# CH32V307WCU6-R0.net
KiCad netlist of a schematic drawn in Altium Designer
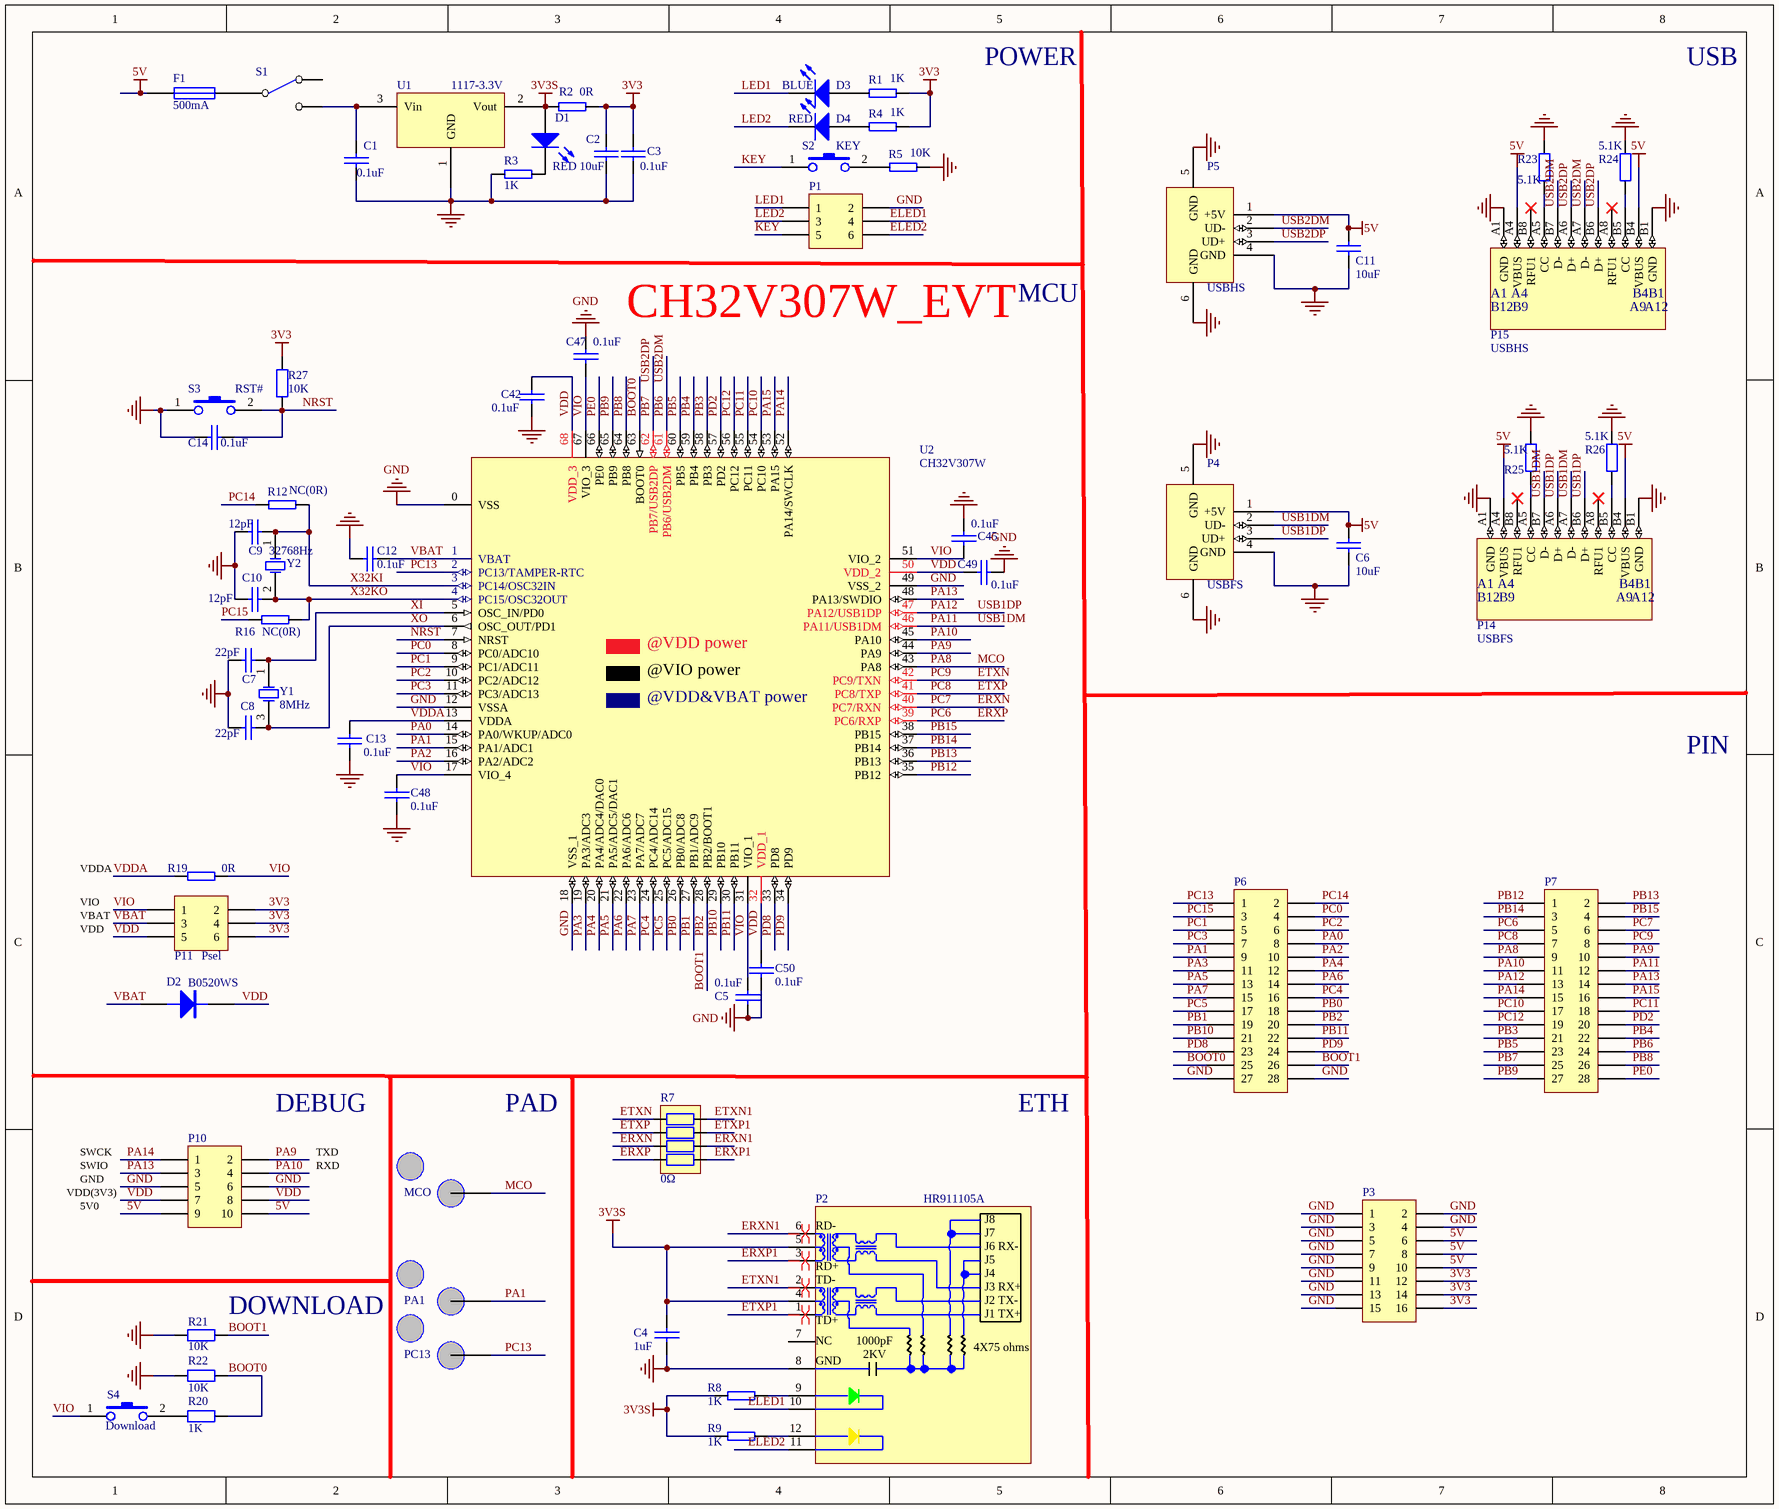
[diagram p0: CH32V307WCU6-R0.SchDoc]

(export (version "E")
  (design (tool "Eeschema 10.0.6"))
  (components
    (comp (ref "C1")
      (value "0.1uF")
      (footprint "0603_C")
      (description "Capacitor")
      (libsource (lib "*") (part "CAP"))
    )
    (comp (ref "C2")
      (value "10uF")
      (footprint "3216_C")
      (description "Capacitor")
      (libsource (lib "*") (part "CAP"))
    )
    (comp (ref "C3")
      (value "0.1uF")
      (footprint "0603_C")
      (description "Capacitor")
      (libsource (lib "*") (part "CAP"))
    )
    (comp (ref "C4")
      (value "1uF")
      (footprint "0603_C")
      (description "Capacitor")
      (libsource (lib "*") (part "CAP"))
    )
    (comp (ref "C5")
      (value "0.1uF")
      (footprint "0603_C")
      (description "Capacitor")
      (libsource (lib "*") (part "CAP"))
    )
    (comp (ref "C6")
      (value "10uF")
      (footprint "3216_C")
      (description "Capacitor")
      (libsource (lib "") (part "CAP_1"))
    )
    (comp (ref "C7")
      (value "22pF")
      (footprint "0603_C")
      (description "Capacitor")
      (libsource (lib "*") (part "CAP"))
    )
    (comp (ref "C8")
      (value "22pF")
      (footprint "0603_C")
      (description "Capacitor")
      (libsource (lib "*") (part "CAP"))
    )
    (comp (ref "C9")
      (value "12pF")
      (footprint "0603_C")
      (description "Capacitor")
      (libsource (lib "*") (part "CAP"))
    )
    (comp (ref "C10")
      (value "12pF")
      (footprint "0603_C")
      (description "Capacitor")
      (libsource (lib "*") (part "CAP"))
    )
    (comp (ref "C11")
      (value "10uF")
      (footprint "3216_C")
      (description "Capacitor")
      (libsource (lib "") (part "CAP_1"))
    )
    (comp (ref "C12")
      (value "0.1uF")
      (footprint "0603_C")
      (description "Capacitor")
      (libsource (lib "*") (part "CAP"))
    )
    (comp (ref "C13")
      (value "0.1uF")
      (footprint "0603_C")
      (description "Capacitor")
      (libsource (lib "*") (part "CAP"))
    )
    (comp (ref "C14")
      (value "0.1uF")
      (footprint "0603_C")
      (description "Capacitor")
      (libsource (lib "") (part "CAP_1"))
    )
    (comp (ref "C42")
      (value "0.1uF")
      (footprint "0603_C")
      (description "Capacitor")
      (libsource (lib "*") (part "CAP"))
    )
    (comp (ref "C45")
      (value "0.1uF")
      (footprint "0603_C")
      (description "Capacitor")
      (libsource (lib "*") (part "CAP"))
    )
    (comp (ref "C47")
      (value "0.1uF")
      (footprint "0603_C")
      (description "Capacitor")
      (libsource (lib "*") (part "CAP"))
    )
    (comp (ref "C48")
      (value "0.1uF")
      (footprint "0603_C")
      (description "Capacitor")
      (libsource (lib "*") (part "CAP"))
    )
    (comp (ref "C49")
      (value "0.1uF")
      (footprint "0603_C")
      (description "Capacitor")
      (libsource (lib "*") (part "CAP"))
    )
    (comp (ref "C50")
      (value "0.1uF")
      (footprint "0603_C")
      (description "Capacitor")
      (libsource (lib "*") (part "CAP"))
    )
    (comp (ref "D1")
      (value "RED")
      (footprint "0603+")
      (description "Typical INFRARED GaAs LED")
      (fields (field (name "PUBLISHER") "Altium Limited"))
      (libsource (lib "*") (part "LED0"))
    )
    (comp (ref "D2")
      (value "B0520WS")
      (footprint "SOD-323")
      (description "Diode")
      (libsource (lib "*") (part "DIODE"))
    )
    (comp (ref "D3")
      (value "BLUE")
      (footprint "0603+")
      (description "Typical INFRARED GaAs LED")
      (fields (field (name "PUBLISHER") "Altium Limited"))
      (libsource (lib "*") (part "LED0"))
    )
    (comp (ref "D4")
      (value "RED")
      (footprint "0603+")
      (description "Typical INFRARED GaAs LED")
      (fields (field (name "PUBLISHER") "Altium Limited"))
      (libsource (lib "*") (part "LED0"))
    )
    (comp (ref "F1")
      (value "500mA")
      (footprint "0603")
      (description "Fuse")
      (libsource (lib "wch_sch_others") (part "FUSE1"))
    )
    (comp (ref "MCO")
      (value "Testpoint")
      (footprint "TESTPOINT1")
      (description "测试点")
      (libsource (lib "wch_sch_others") (part "Testpoint"))
    )
    (comp (ref "P1")
      (value "IO")
      (footprint "IDC6-2.54mm")
      (description "Header, 3-Pin, Dual row, Right Angle")
      (fields (field (name "PUBLISHER") "Altium Limited"))
      (libsource (lib "Miscellaneous Connectors") (part "Header 3X2H"))
    )
    (comp (ref "P2") (value "HR911105A") (footprint "HR911105A") (libsource (lib "*") (part "HR911105A")))
    (comp (ref "P3")
      (value "Ppin")
      (footprint "IDC16-2.54mm")
      (description "Header, 8-Pin, Dual row, Right Angle")
      (fields (field (name "PUBLISHER") "Altium Limited"))
      (libsource (lib "Miscellaneous Connectors") (part "Header 8X2H"))
    )
    (comp (ref "P4")
      (value "USBFS")
      (footprint "USBAF")
      (description "USB Port")
      (libsource (lib "*") (part "USB"))
    )
    (comp (ref "P5")
      (value "USBHS")
      (footprint "USBAF")
      (description "USB Port")
      (libsource (lib "*") (part "USB"))
    )
    (comp (ref "P6")
      (value "HEADER 14x2")
      (footprint "MYPCB:IDC28-2.54MM")
      (description "Header, 14-Pin, Dual row")
      (libsource (lib "wch_sch_others") (part "HEADER 14x2"))
    )
    (comp (ref "P7")
      (value "HEADER 14x2")
      (footprint "MYPCB:IDC28-2.54MM")
      (description "Header, 14-Pin, Dual row")
      (libsource (lib "wch_sch_others") (part "HEADER 14x2"))
    )
    (comp (ref "P10")
      (value "LINK")
      (footprint "IDC10-2.54mm")
      (description "Header, 5-Pin, Dual row, Right Angle")
      (fields (field (name "PUBLISHER") "Altium Limited"))
      (libsource (lib "Miscellaneous Connectors") (part "Header 5X2H"))
    )
    (comp (ref "P11")
      (value "Psel")
      (footprint "IDC6-2.54mm")
      (description "Header, 3-Pin, Dual row, Right Angle")
      (fields (field (name "PUBLISHER") "Altium Limited"))
      (libsource (lib "Miscellaneous Connectors") (part "Header 3X2H"))
    )
    (comp (ref "P14")
      (value "USBFS")
      (footprint "TYPE-C-Receptacle-2.0")
      (libsource (lib "*") (part "TYPE-C1"))
    )
    (comp (ref "P15")
      (value "USBHS")
      (footprint "TYPE-C-Receptacle-2.0")
      (libsource (lib "*") (part "TYPE-C1"))
    )
    (comp (ref "PA1")
      (value "Testpoint")
      (footprint "TESTPOINT1")
      (description "测试点")
      (libsource (lib "wch_sch_others") (part "Testpoint"))
    )
    (comp (ref "PC13")
      (value "Testpoint")
      (footprint "TESTPOINT1")
      (description "测试点")
      (libsource (lib "wch_sch_others") (part "Testpoint"))
    )
    (comp (ref "R1") (value "1K") (footprint "0603") (libsource (lib "wch_sch_others") (part "RES")))
    (comp (ref "R2") (value "0R") (footprint "0603") (libsource (lib "wch_sch_others") (part "RES")))
    (comp (ref "R3") (value "1K") (footprint "0603") (libsource (lib "wch_sch_others") (part "RES")))
    (comp (ref "R4") (value "1K") (footprint "0603") (libsource (lib "wch_sch_others") (part "RES")))
    (comp (ref "R5") (value "10K") (footprint "0603") (libsource (lib "wch_sch_others") (part "RES")))
    (comp (ref "R7")
      (value "0Ω")
      (footprint "8P4R-0603")
      (description "贴片网络排阻")
      (fields (field (name "版权归属") "源创客"))
      (libsource (lib "wch_sch_others") (part "R-8P4R"))
    )
    (comp (ref "R8") (value "1K") (footprint "0603") (libsource (lib "wch_sch_others") (part "RES")))
    (comp (ref "R9") (value "1K") (footprint "0603") (libsource (lib "wch_sch_others") (part "RES")))
    (comp (ref "R12") (value "NC(0R)") (footprint "0603") (libsource (lib "wch_sch_others") (part "RES")))
    (comp (ref "R16") (value "NC(0R)") (footprint "0603") (libsource (lib "wch_sch_others") (part "RES")))
    (comp (ref "R19") (value "0R") (footprint "0603") (libsource (lib "*") (part "R")))
    (comp (ref "R20")
      (value "1K")
      (footprint "0603")
      (description "Resistor")
      (fields (field (name "PUBLISHER") "Altium Limited"))
      (libsource (lib "Miscellaneous Devices") (part "Res2"))
    )
    (comp (ref "R21")
      (value "10K")
      (footprint "0603")
      (description "Resistor")
      (fields (field (name "PUBLISHER") "Altium Limited"))
      (libsource (lib "Miscellaneous Devices") (part "Res2"))
    )
    (comp (ref "R22")
      (value "10K")
      (footprint "0603")
      (description "Resistor")
      (fields (field (name "PUBLISHER") "Altium Limited"))
      (libsource (lib "Miscellaneous Devices") (part "Res2"))
    )
    (comp (ref "R23")
      (value "5.1K")
      (footprint "0603")
      (description "Resistor")
      (libsource (lib "") (part "Res2_1"))
    )
    (comp (ref "R24")
      (value "5.1K")
      (footprint "0603")
      (description "Resistor")
      (libsource (lib "") (part "Res2_1"))
    )
    (comp (ref "R25")
      (value "5.1K")
      (footprint "0603")
      (description "Resistor")
      (libsource (lib "") (part "Res2_1"))
    )
    (comp (ref "R26")
      (value "5.1K")
      (footprint "0603")
      (description "Resistor")
      (libsource (lib "") (part "Res2_1"))
    )
    (comp (ref "R27")
      (value "10K")
      (footprint "0603")
      (description "Resistor")
      (fields (field (name "PUBLISHER") "Altium Limited"))
      (libsource (lib "") (part "Res2_1"))
    )
    (comp (ref "S1") (value "SW SPDT") (footprint "KEY2") (libsource (lib "*") (part "SW SPDT")))
    (comp (ref "S2")
      (value "KEY")
      (footprint "SMD_6.1x3.65x2.5mm-KEY")
      (libsource (lib "wch_sch_others") (part "KEY1"))
    )
    (comp (ref "S3")
      (value "RST#")
      (footprint "SMD_6.1x3.65x2.5mm-KEY")
      (libsource (lib "wch_sch_others") (part "KEY1"))
    )
    (comp (ref "S4")
      (value "Download")
      (footprint "SMD_6.1x3.65x2.5mm-KEY")
      (libsource (lib "wch_sch_others") (part "KEY1"))
    )
    (comp (ref "U1")
      (value "1117-3.3V")
      (footprint "SOT-223")
      (libsource (lib "wch_sch_others") (part "1117-3.3V"))
    )
    (comp (ref "U2")
      (value "CH32V307W")
      (footprint "QFN68_8x8")
      (description "RISC-V FPU HD-MCU, 144MHz, USB_480M, USB OTG, 1000M Ethernet MAC, 2*CAN")
      (libsource (lib "CHXXX") (part "CH32V307W"))
    )
    (comp (ref "Y1")
      (value "8MHz")
      (footprint "XT3225")
      (description "Crystal Oscillator")
      (fields (field (name "PUBLISHER") "Altium Limited"))
      (libsource (lib "*") (part "XTAL"))
    )
    (comp (ref "Y2")
      (value "32768Hz")
      (footprint "FC-135")
      (description "Crystal Oscillator")
      (fields (field (name "PUBLISHER") "Altium Limited"))
      (libsource (lib "") (part "XTAL_1"))
    )
  )
  (nets
    (net (code "2") (name "/BOOT0") (class "Default")
      (node (ref "P6") (pin "25") (pinfunction "25_25") (pintype "passive"))
      (node (ref "R20") (pin "1") (pinfunction "1_1") (pintype "passive"))
      (node (ref "R22") (pin "1") (pinfunction "1_1") (pintype "passive"))
      (node (ref "U2") (pin "63") (pinfunction "BOOT0_63") (pintype "input"))
    )
    (net (code "3") (name "/BOOT1") (class "Default")
      (node (ref "P6") (pin "20") (pinfunction "20_20") (pintype "passive"))
      (node (ref "P6") (pin "26") (pinfunction "26_26") (pintype "passive"))
      (node (ref "R21") (pin "1") (pinfunction "1_1") (pintype "passive"))
      (node (ref "U2") (pin "28") (pinfunction "PB2/BOOT1_28") (pintype "bidirectional"))
    )
    (net (code "4") (name "/ELED1") (class "Default")
      (node (ref "P1") (pin "4") (pinfunction "4_4") (pintype "passive"))
      (node (ref "P2") (pin "10") (pintype "passive"))
    )
    (net (code "5") (name "/ELED2") (class "Default")
      (node (ref "P1") (pin "6") (pinfunction "6_6") (pintype "passive"))
      (node (ref "P2") (pin "11") (pintype "passive"))
    )
    (net (code "6") (name "/ERXN") (class "Default")
      (node (ref "P7") (pin "6") (pinfunction "6_6") (pintype "passive"))
      (node (ref "R7") (pin "3") (pinfunction "3_3") (pintype "passive"))
      (node (ref "U2") (pin "40") (pinfunction "PC7/RXN_40") (pintype "bidirectional"))
    )
    (net (code "7") (name "/ERXN1") (class "Default")
      (node (ref "P2") (pin "6") (pintype "passive"))
      (node (ref "R7") (pin "6") (pinfunction "6_6") (pintype "passive"))
    )
    (net (code "8") (name "/ERXP") (class "Default")
      (node (ref "P7") (pin "5") (pinfunction "5_5") (pintype "passive"))
      (node (ref "R7") (pin "4") (pinfunction "4_4") (pintype "passive"))
      (node (ref "U2") (pin "39") (pinfunction "PC6/RXP_39") (pintype "bidirectional"))
    )
    (net (code "9") (name "/ERXP1") (class "Default")
      (node (ref "P2") (pin "3") (pintype "passive"))
      (node (ref "R7") (pin "5") (pinfunction "5_5") (pintype "passive"))
    )
    (net (code "10") (name "/ETXN") (class "Default")
      (node (ref "P7") (pin "8") (pinfunction "8_8") (pintype "passive"))
      (node (ref "R7") (pin "1") (pinfunction "1_1") (pintype "passive"))
      (node (ref "U2") (pin "42") (pinfunction "PC9/TXN_42") (pintype "bidirectional"))
    )
    (net (code "11") (name "/ETXN1") (class "Default")
      (node (ref "P2") (pin "2") (pintype "passive"))
      (node (ref "R7") (pin "8") (pinfunction "8_8") (pintype "passive"))
    )
    (net (code "12") (name "/ETXP") (class "Default")
      (node (ref "P7") (pin "7") (pinfunction "7_7") (pintype "passive"))
      (node (ref "R7") (pin "2") (pinfunction "2_2") (pintype "passive"))
      (node (ref "U2") (pin "41") (pinfunction "PC8/TXP_41") (pintype "bidirectional"))
    )
    (net (code "13") (name "/ETXP1") (class "Default")
      (node (ref "P2") (pin "1") (pintype "passive"))
      (node (ref "R7") (pin "7") (pinfunction "7_7") (pintype "passive"))
    )
    (net (code "14") (name "/KEY") (class "Default")
      (node (ref "P1") (pin "5") (pinfunction "5_5") (pintype "passive"))
      (node (ref "S2") (pin "1") (pinfunction "1_1") (pintype "passive"))
    )
    (net (code "15") (name "/LED1") (class "Default")
      (node (ref "D3") (pin "2") (pinfunction "K_2") (pintype "passive"))
      (node (ref "P1") (pin "1") (pinfunction "1_1") (pintype "passive"))
    )
    (net (code "16") (name "/LED2") (class "Default")
      (node (ref "D4") (pin "2") (pinfunction "K_2") (pintype "passive"))
      (node (ref "P1") (pin "3") (pinfunction "3_3") (pintype "passive"))
    )
    (net (code "17") (name "/MCO") (class "Default")
      (node (ref "MCO") (pin "1") (pinfunction "point_1") (pintype "passive"))
      (node (ref "P7") (pin "9") (pinfunction "9_9") (pintype "passive"))
      (node (ref "U2") (pin "43") (pinfunction "PA8_43") (pintype "bidirectional"))
    )
    (net (code "18") (name "/NRST") (class "Default")
      (node (ref "C14") (pin "2") (pinfunction "2_2") (pintype "passive"))
      (node (ref "R27") (pin "1") (pinfunction "1_1") (pintype "passive"))
      (node (ref "S3") (pin "2") (pinfunction "2_2") (pintype "passive"))
      (node (ref "U2") (pin "7") (pinfunction "NRST_7") (pintype "input"))
    )
    (net (code "19") (name "/PA0") (class "Default")
      (node (ref "P6") (pin "8") (pinfunction "8_8") (pintype "passive"))
      (node (ref "U2") (pin "14") (pinfunction "PA0/WKUP/ADC0_14") (pintype "bidirectional"))
    )
    (net (code "20") (name "/PA1") (class "Default")
      (node (ref "P6") (pin "9") (pinfunction "9_9") (pintype "passive"))
      (node (ref "PA1") (pin "1") (pinfunction "point_1") (pintype "passive"))
      (node (ref "U2") (pin "15") (pinfunction "PA1/ADC1_15") (pintype "bidirectional"))
    )
    (net (code "21") (name "/PA2") (class "Default")
      (node (ref "P6") (pin "10") (pinfunction "10_10") (pintype "passive"))
      (node (ref "U2") (pin "16") (pinfunction "PA2/ADC2_16") (pintype "bidirectional"))
    )
    (net (code "22") (name "/PA3") (class "Default")
      (node (ref "P6") (pin "11") (pinfunction "11_11") (pintype "passive"))
      (node (ref "U2") (pin "19") (pinfunction "PA3/ADC3_19") (pintype "bidirectional"))
    )
    (net (code "23") (name "/PA4") (class "Default")
      (node (ref "P6") (pin "12") (pinfunction "12_12") (pintype "passive"))
      (node (ref "U2") (pin "20") (pinfunction "PA4/ADC4/DAC0_20") (pintype "bidirectional"))
    )
    (net (code "24") (name "/PA5") (class "Default")
      (node (ref "P6") (pin "13") (pinfunction "13_13") (pintype "passive"))
      (node (ref "U2") (pin "21") (pinfunction "PA5/ADC5/DAC1_21") (pintype "bidirectional"))
    )
    (net (code "25") (name "/PA6") (class "Default")
      (node (ref "P6") (pin "14") (pinfunction "14_14") (pintype "passive"))
      (node (ref "U2") (pin "22") (pinfunction "PA6/ADC6_22") (pintype "bidirectional"))
    )
    (net (code "26") (name "/PA7") (class "Default")
      (node (ref "P6") (pin "15") (pinfunction "15_15") (pintype "passive"))
      (node (ref "U2") (pin "23") (pinfunction "PA7/ADC7_23") (pintype "bidirectional"))
    )
    (net (code "27") (name "/PA9") (class "Default")
      (node (ref "P10") (pin "2") (pinfunction "2_2") (pintype "passive"))
      (node (ref "P7") (pin "10") (pinfunction "10_10") (pintype "passive"))
      (node (ref "U2") (pin "44") (pinfunction "PA9_44") (pintype "bidirectional"))
    )
    (net (code "28") (name "/PA10") (class "Default")
      (node (ref "P10") (pin "4") (pinfunction "4_4") (pintype "passive"))
      (node (ref "P7") (pin "11") (pinfunction "11_11") (pintype "passive"))
      (node (ref "U2") (pin "45") (pinfunction "PA10_45") (pintype "bidirectional"))
    )
    (net (code "29") (name "/PA11") (class "Default")
      (node (ref "P14") (pin "A7") (pinfunction "D-_A7") (pintype "bidirectional"))
      (node (ref "P14") (pin "B7") (pinfunction "D-_B7") (pintype "bidirectional"))
      (node (ref "P4") (pin "2") (pinfunction "UD-_2") (pintype "bidirectional"))
      (node (ref "P7") (pin "12") (pinfunction "12_12") (pintype "passive"))
      (node (ref "U2") (pin "46") (pinfunction "PA11/USB1DM_46") (pintype "bidirectional"))
    )
    (net (code "30") (name "/PA12") (class "Default")
      (node (ref "P14") (pin "A6") (pinfunction "D+_A6") (pintype "bidirectional"))
      (node (ref "P14") (pin "B6") (pinfunction "D+_B6") (pintype "bidirectional"))
      (node (ref "P4") (pin "3") (pinfunction "UD+_3") (pintype "bidirectional"))
      (node (ref "P7") (pin "13") (pinfunction "13_13") (pintype "passive"))
      (node (ref "U2") (pin "47") (pinfunction "PA12/USB1DP_47") (pintype "bidirectional"))
    )
    (net (code "31") (name "/PA13") (class "Default")
      (node (ref "P10") (pin "3") (pinfunction "3_3") (pintype "passive"))
      (node (ref "P7") (pin "14") (pinfunction "14_14") (pintype "passive"))
      (node (ref "U2") (pin "48") (pinfunction "PA13/SWDIO_48") (pintype "bidirectional"))
    )
    (net (code "32") (name "/PA14") (class "Default")
      (node (ref "P10") (pin "1") (pinfunction "1_1") (pintype "passive"))
      (node (ref "P7") (pin "15") (pinfunction "15_15") (pintype "passive"))
      (node (ref "U2") (pin "52") (pinfunction "PA14/SWCLK_52") (pintype "bidirectional"))
    )
    (net (code "33") (name "/PA15") (class "Default")
      (node (ref "P7") (pin "16") (pinfunction "16_16") (pintype "passive"))
      (node (ref "U2") (pin "53") (pinfunction "PA15_53") (pintype "bidirectional"))
    )
    (net (code "34") (name "/PB0") (class "Default")
      (node (ref "P6") (pin "18") (pinfunction "18_18") (pintype "passive"))
      (node (ref "U2") (pin "26") (pinfunction "PB0/ADC8_26") (pintype "bidirectional"))
    )
    (net (code "35") (name "/PB1") (class "Default")
      (node (ref "P6") (pin "19") (pinfunction "19_19") (pintype "passive"))
      (node (ref "U2") (pin "27") (pinfunction "PB1/ADC9_27") (pintype "bidirectional"))
    )
    (net (code "36") (name "/PB3") (class "Default")
      (node (ref "P7") (pin "21") (pinfunction "21_21") (pintype "passive"))
      (node (ref "U2") (pin "58") (pinfunction "PB3_58") (pintype "bidirectional"))
    )
    (net (code "37") (name "/PB4") (class "Default")
      (node (ref "P7") (pin "22") (pinfunction "22_22") (pintype "passive"))
      (node (ref "U2") (pin "59") (pinfunction "PB4_59") (pintype "bidirectional"))
    )
    (net (code "38") (name "/PB5") (class "Default")
      (node (ref "P7") (pin "23") (pinfunction "23_23") (pintype "passive"))
      (node (ref "U2") (pin "60") (pinfunction "PB5_60") (pintype "bidirectional"))
    )
    (net (code "39") (name "/PB6") (class "Default")
      (node (ref "P15") (pin "A7") (pinfunction "D-_A7") (pintype "bidirectional"))
      (node (ref "P15") (pin "B7") (pinfunction "D-_B7") (pintype "bidirectional"))
      (node (ref "P5") (pin "2") (pinfunction "UD-_2") (pintype "bidirectional"))
      (node (ref "P7") (pin "24") (pinfunction "24_24") (pintype "passive"))
      (node (ref "U2") (pin "61") (pinfunction "PB6/USB2DM_61") (pintype "bidirectional"))
    )
    (net (code "40") (name "/PB7") (class "Default")
      (node (ref "P15") (pin "A6") (pinfunction "D+_A6") (pintype "bidirectional"))
      (node (ref "P15") (pin "B6") (pinfunction "D+_B6") (pintype "bidirectional"))
      (node (ref "P5") (pin "3") (pinfunction "UD+_3") (pintype "bidirectional"))
      (node (ref "P7") (pin "25") (pinfunction "25_25") (pintype "passive"))
      (node (ref "U2") (pin "62") (pinfunction "PB7/USB2DP_62") (pintype "bidirectional"))
    )
    (net (code "41") (name "/PB8") (class "Default")
      (node (ref "P7") (pin "26") (pinfunction "26_26") (pintype "passive"))
      (node (ref "U2") (pin "64") (pinfunction "PB8_64") (pintype "bidirectional"))
    )
    (net (code "42") (name "/PB9") (class "Default")
      (node (ref "P7") (pin "27") (pinfunction "27_27") (pintype "passive"))
      (node (ref "U2") (pin "65") (pinfunction "PB9_65") (pintype "bidirectional"))
    )
    (net (code "43") (name "/PB10") (class "Default")
      (node (ref "P6") (pin "21") (pinfunction "21_21") (pintype "passive"))
      (node (ref "U2") (pin "29") (pinfunction "PB10_29") (pintype "bidirectional"))
    )
    (net (code "44") (name "/PB11") (class "Default")
      (node (ref "P6") (pin "22") (pinfunction "22_22") (pintype "passive"))
      (node (ref "U2") (pin "30") (pinfunction "PB11_30") (pintype "bidirectional"))
    )
    (net (code "45") (name "/PB12") (class "Default")
      (node (ref "P7") (pin "1") (pinfunction "1_1") (pintype "passive"))
      (node (ref "U2") (pin "35") (pinfunction "PB12_35") (pintype "bidirectional"))
    )
    (net (code "46") (name "/PB13") (class "Default")
      (node (ref "P7") (pin "2") (pinfunction "2_2") (pintype "passive"))
      (node (ref "U2") (pin "36") (pinfunction "PB13_36") (pintype "bidirectional"))
    )
    (net (code "47") (name "/PB14") (class "Default")
      (node (ref "P7") (pin "3") (pinfunction "3_3") (pintype "passive"))
      (node (ref "U2") (pin "37") (pinfunction "PB14_37") (pintype "bidirectional"))
    )
    (net (code "48") (name "/PB15") (class "Default")
      (node (ref "P7") (pin "4") (pinfunction "4_4") (pintype "passive"))
      (node (ref "U2") (pin "38") (pinfunction "PB15_38") (pintype "bidirectional"))
    )
    (net (code "49") (name "/PC0") (class "Default")
      (node (ref "P6") (pin "4") (pinfunction "4_4") (pintype "passive"))
      (node (ref "U2") (pin "8") (pinfunction "PC0/ADC10_8") (pintype "bidirectional"))
    )
    (net (code "50") (name "/PC1") (class "Default")
      (node (ref "P6") (pin "5") (pinfunction "5_5") (pintype "passive"))
      (node (ref "U2") (pin "9") (pinfunction "PC1/ADC11_9") (pintype "bidirectional"))
    )
    (net (code "51") (name "/PC2") (class "Default")
      (node (ref "P6") (pin "6") (pinfunction "6_6") (pintype "passive"))
      (node (ref "U2") (pin "10") (pinfunction "PC2/ADC12_10") (pintype "bidirectional"))
    )
    (net (code "52") (name "/PC3") (class "Default")
      (node (ref "P6") (pin "7") (pinfunction "7_7") (pintype "passive"))
      (node (ref "U2") (pin "11") (pinfunction "PC3/ADC13_11") (pintype "bidirectional"))
    )
    (net (code "53") (name "/PC4") (class "Default")
      (node (ref "P6") (pin "16") (pinfunction "16_16") (pintype "passive"))
      (node (ref "U2") (pin "24") (pinfunction "PC4/ADC14_24") (pintype "bidirectional"))
    )
    (net (code "54") (name "/PC5") (class "Default")
      (node (ref "P6") (pin "17") (pinfunction "17_17") (pintype "passive"))
      (node (ref "U2") (pin "25") (pinfunction "PC5/ADC15_25") (pintype "bidirectional"))
    )
    (net (code "55") (name "/PC10") (class "Default")
      (node (ref "P7") (pin "17") (pinfunction "17_17") (pintype "passive"))
      (node (ref "U2") (pin "54") (pinfunction "PC10_54") (pintype "bidirectional"))
    )
    (net (code "56") (name "/PC11") (class "Default")
      (node (ref "P7") (pin "18") (pinfunction "18_18") (pintype "passive"))
      (node (ref "U2") (pin "55") (pinfunction "PC11_55") (pintype "bidirectional"))
    )
    (net (code "57") (name "/PC12") (class "Default")
      (node (ref "P7") (pin "19") (pinfunction "19_19") (pintype "passive"))
      (node (ref "U2") (pin "56") (pinfunction "PC12_56") (pintype "bidirectional"))
    )
    (net (code "58") (name "/PC13") (class "Default")
      (node (ref "P6") (pin "1") (pinfunction "1_1") (pintype "passive"))
      (node (ref "PC13") (pin "1") (pinfunction "point_1") (pintype "passive"))
      (node (ref "U2") (pin "2") (pinfunction "PC13/TAMPER-RTC_2") (pintype "bidirectional"))
    )
    (net (code "59") (name "/PC14") (class "Default")
      (node (ref "P6") (pin "2") (pinfunction "2_2") (pintype "passive"))
      (node (ref "R12") (pin "1") (pintype "passive"))
    )
    (net (code "60") (name "/PC15") (class "Default")
      (node (ref "P6") (pin "3") (pinfunction "3_3") (pintype "passive"))
      (node (ref "R16") (pin "1") (pintype "passive"))
    )
    (net (code "61") (name "/PD2") (class "Default")
      (node (ref "P7") (pin "20") (pinfunction "20_20") (pintype "passive"))
      (node (ref "U2") (pin "57") (pinfunction "PD2_57") (pintype "bidirectional"))
    )
    (net (code "62") (name "/PD8") (class "Default")
      (node (ref "P6") (pin "23") (pinfunction "23_23") (pintype "passive"))
      (node (ref "U2") (pin "33") (pinfunction "PD8_33") (pintype "bidirectional"))
    )
    (net (code "63") (name "/PD9") (class "Default")
      (node (ref "P6") (pin "24") (pinfunction "24_24") (pintype "passive"))
      (node (ref "U2") (pin "34") (pinfunction "PD9_34") (pintype "bidirectional"))
    )
    (net (code "64") (name "/PE0") (class "Default")
      (node (ref "P7") (pin "28") (pinfunction "28_28") (pintype "passive"))
      (node (ref "U2") (pin "66") (pinfunction "PE0_66") (pintype "bidirectional"))
    )
    (net (code "65") (name "/VBAT") (class "Default")
      (node (ref "C12") (pin "2") (pinfunction "2_2") (pintype "passive"))
      (node (ref "D2") (pin "1") (pinfunction "A_1") (pintype "passive"))
      (node (ref "P11") (pin "3") (pinfunction "3_3") (pintype "passive"))
      (node (ref "U2") (pin "1") (pinfunction "VBAT_1") (pintype "power_in"))
    )
    (net (code "66") (name "/VDD") (class "Default")
      (node (ref "C42") (pin "2") (pinfunction "2_2") (pintype "passive"))
      (node (ref "C49") (pin "2") (pinfunction "2_2") (pintype "passive"))
      (node (ref "C50") (pin "1") (pinfunction "1_1") (pintype "passive"))
      (node (ref "D2") (pin "2") (pinfunction "K_2") (pintype "passive"))
      (node (ref "P10") (pin "7") (pinfunction "7_7") (pintype "passive"))
      (node (ref "P10") (pin "8") (pinfunction "8_8") (pintype "passive"))
      (node (ref "P11") (pin "5") (pinfunction "5_5") (pintype "passive"))
      (node (ref "U2") (pin "32") (pinfunction "VDD_1_32") (pintype "power_in"))
      (node (ref "U2") (pin "50") (pinfunction "VDD_2_50") (pintype "power_in"))
      (node (ref "U2") (pin "68") (pinfunction "VDD_3_68") (pintype "power_in"))
    )
    (net (code "67") (name "/VDDA") (class "Default")
      (node (ref "C13") (pin "1") (pinfunction "1_1") (pintype "passive"))
      (node (ref "R19") (pin "2") (pinfunction "2_2") (pintype "passive"))
      (node (ref "U2") (pin "13") (pinfunction "VDDA_13") (pintype "power_in"))
    )
    (net (code "68") (name "/VIO") (class "Default")
      (node (ref "C45") (pin "1") (pinfunction "1_1") (pintype "passive"))
      (node (ref "C47") (pin "1") (pinfunction "1_1") (pintype "passive"))
      (node (ref "C48") (pin "1") (pinfunction "1_1") (pintype "passive"))
      (node (ref "C5") (pin "2") (pinfunction "2_2") (pintype "passive"))
      (node (ref "P11") (pin "1") (pinfunction "1_1") (pintype "passive"))
      (node (ref "R19") (pin "1") (pinfunction "1_1") (pintype "passive"))
      (node (ref "S4") (pin "1") (pinfunction "1_1") (pintype "passive"))
      (node (ref "U2") (pin "17") (pinfunction "VIO_4_17") (pintype "power_in"))
      (node (ref "U2") (pin "31") (pinfunction "VIO_1_31") (pintype "power_in"))
      (node (ref "U2") (pin "51") (pinfunction "VIO_2_51") (pintype "power_in"))
      (node (ref "U2") (pin "67") (pinfunction "VIO_3_67") (pintype "power_in"))
    )
    (net (code "69") (name "/X32KI") (class "Default")
      (node (ref "C9") (pin "2") (pinfunction "2_2") (pintype "passive"))
      (node (ref "R12") (pin "2") (pintype "passive"))
      (node (ref "U2") (pin "3") (pinfunction "PC14/OSC32IN_3") (pintype "bidirectional"))
      (node (ref "Y2") (pin "1") (pinfunction "OSC1_1") (pintype "passive"))
    )
    (net (code "70") (name "/X32KO") (class "Default")
      (node (ref "C10") (pin "2") (pinfunction "2_2") (pintype "passive"))
      (node (ref "R16") (pin "2") (pintype "passive"))
      (node (ref "U2") (pin "4") (pinfunction "PC15/OSC32OUT_4") (pintype "bidirectional"))
      (node (ref "Y2") (pin "2") (pinfunction "OSC2_2") (pintype "passive"))
    )
    (net (code "71") (name "/XI") (class "Default")
      (node (ref "C7") (pin "2") (pinfunction "2_2") (pintype "passive"))
      (node (ref "U2") (pin "5") (pinfunction "OSC_IN/PD0_5") (pintype "input"))
      (node (ref "Y1") (pin "1") (pinfunction "OSC1_1") (pintype "passive"))
    )
    (net (code "72") (name "/XO") (class "Default")
      (node (ref "C8") (pin "2") (pinfunction "2_2") (pintype "passive"))
      (node (ref "U2") (pin "6") (pinfunction "OSC_OUT/PD1_6") (pintype "output"))
      (node (ref "Y1") (pin "3") (pinfunction "OSC2_3") (pintype "passive"))
    )
    (net (code "73") (name "3V3") (class "Default")
      (node (ref "C2") (pin "1") (pinfunction "1_1") (pintype "passive"))
      (node (ref "C3") (pin "1") (pinfunction "1_1") (pintype "passive"))
      (node (ref "P11") (pin "2") (pinfunction "2_2") (pintype "passive"))
      (node (ref "P11") (pin "4") (pinfunction "4_4") (pintype "passive"))
      (node (ref "P11") (pin "6") (pinfunction "6_6") (pintype "passive"))
      (node (ref "P3") (pin "12") (pinfunction "12_12") (pintype "passive"))
      (node (ref "P3") (pin "14") (pinfunction "14_14") (pintype "passive"))
      (node (ref "P3") (pin "16") (pinfunction "16_16") (pintype "passive"))
      (node (ref "R1") (pin "1") (pintype "passive"))
      (node (ref "R2") (pin "1") (pintype "passive"))
      (node (ref "R27") (pin "2") (pinfunction "2_2") (pintype "passive"))
      (node (ref "R4") (pin "1") (pintype "passive"))
    )
    (net (code "74") (name "3V3S") (class "Default")
      (node (ref "C4") (pin "2") (pinfunction "2_2") (pintype "passive"))
      (node (ref "D1") (pin "1") (pinfunction "A_1") (pintype "passive"))
      (node (ref "P2") (pin "4") (pintype "passive"))
      (node (ref "P2") (pin "5") (pintype "passive"))
      (node (ref "R2") (pin "2") (pintype "passive"))
      (node (ref "R8") (pin "1") (pintype "passive"))
      (node (ref "R9") (pin "1") (pintype "passive"))
      (node (ref "U1") (pin "2") (pinfunction "Vout_2") (pintype "passive"))
    )
    (net (code "75") (name "5V") (class "Default")
      (node (ref "C11") (pin "1") (pinfunction "1_1") (pintype "passive"))
      (node (ref "C6") (pin "1") (pinfunction "1_1") (pintype "passive"))
      (node (ref "F1") (pin "1") (pinfunction "1_1") (pintype "passive"))
      (node (ref "P10") (pin "10") (pinfunction "10_10") (pintype "passive"))
      (node (ref "P10") (pin "9") (pinfunction "9_9") (pintype "passive"))
      (node (ref "P14") (pin "A4") (pinfunction "VBUS_A4") (pintype "bidirectional"))
      (node (ref "P14") (pin "B4") (pinfunction "VBUS_B4") (pintype "bidirectional"))
      (node (ref "P15") (pin "A4") (pinfunction "VBUS_A4") (pintype "bidirectional"))
      (node (ref "P15") (pin "B4") (pinfunction "VBUS_B4") (pintype "bidirectional"))
      (node (ref "P3") (pin "10") (pinfunction "10_10") (pintype "passive"))
      (node (ref "P3") (pin "6") (pinfunction "6_6") (pintype "passive"))
      (node (ref "P3") (pin "8") (pinfunction "8_8") (pintype "passive"))
      (node (ref "P4") (pin "1") (pinfunction "+5V_1") (pintype "power_in"))
      (node (ref "P5") (pin "1") (pinfunction "+5V_1") (pintype "power_in"))
    )
    (net (code "76") (name "GND") (class "Default")
      (node (ref "C1") (pin "2") (pinfunction "2_2") (pintype "passive"))
      (node (ref "C10") (pin "1") (pinfunction "1_1") (pintype "passive"))
      (node (ref "C11") (pin "2") (pinfunction "2_2") (pintype "passive"))
      (node (ref "C12") (pin "1") (pinfunction "1_1") (pintype "passive"))
      (node (ref "C13") (pin "2") (pinfunction "2_2") (pintype "passive"))
      (node (ref "C14") (pin "1") (pinfunction "1_1") (pintype "passive"))
      (node (ref "C2") (pin "2") (pinfunction "2_2") (pintype "passive"))
      (node (ref "C3") (pin "2") (pinfunction "2_2") (pintype "passive"))
      (node (ref "C4") (pin "1") (pinfunction "1_1") (pintype "passive"))
      (node (ref "C42") (pin "1") (pinfunction "1_1") (pintype "passive"))
      (node (ref "C45") (pin "2") (pinfunction "2_2") (pintype "passive"))
      (node (ref "C47") (pin "2") (pinfunction "2_2") (pintype "passive"))
      (node (ref "C48") (pin "2") (pinfunction "2_2") (pintype "passive"))
      (node (ref "C49") (pin "1") (pinfunction "1_1") (pintype "passive"))
      (node (ref "C5") (pin "1") (pinfunction "1_1") (pintype "passive"))
      (node (ref "C50") (pin "2") (pinfunction "2_2") (pintype "passive"))
      (node (ref "C6") (pin "2") (pinfunction "2_2") (pintype "passive"))
      (node (ref "C7") (pin "1") (pinfunction "1_1") (pintype "passive"))
      (node (ref "C8") (pin "1") (pinfunction "1_1") (pintype "passive"))
      (node (ref "C9") (pin "1") (pinfunction "1_1") (pintype "passive"))
      (node (ref "P1") (pin "2") (pinfunction "2_2") (pintype "passive"))
      (node (ref "P10") (pin "5") (pinfunction "5_5") (pintype "passive"))
      (node (ref "P10") (pin "6") (pinfunction "6_6") (pintype "passive"))
      (node (ref "P14") (pin "A1") (pinfunction "GND_A1") (pintype "bidirectional"))
      (node (ref "P14") (pin "B1") (pinfunction "GND_B1") (pintype "bidirectional"))
      (node (ref "P15") (pin "A1") (pinfunction "GND_A1") (pintype "bidirectional"))
      (node (ref "P15") (pin "B1") (pinfunction "GND_B1") (pintype "bidirectional"))
      (node (ref "P2") (pin "8") (pintype "passive"))
      (node (ref "P3") (pin "1") (pinfunction "1_1") (pintype "passive"))
      (node (ref "P3") (pin "11") (pinfunction "11_11") (pintype "passive"))
      (node (ref "P3") (pin "13") (pinfunction "13_13") (pintype "passive"))
      (node (ref "P3") (pin "15") (pinfunction "15_15") (pintype "passive"))
      (node (ref "P3") (pin "2") (pinfunction "2_2") (pintype "passive"))
      (node (ref "P3") (pin "3") (pinfunction "3_3") (pintype "passive"))
      (node (ref "P3") (pin "4") (pinfunction "4_4") (pintype "passive"))
      (node (ref "P3") (pin "5") (pinfunction "5_5") (pintype "passive"))
      (node (ref "P3") (pin "7") (pinfunction "7_7") (pintype "passive"))
      (node (ref "P3") (pin "9") (pinfunction "9_9") (pintype "passive"))
      (node (ref "P4") (pin "4") (pinfunction "GND_4") (pintype "power_in"))
      (node (ref "P4") (pin "5") (pinfunction "GND_5") (pintype "power_in"))
      (node (ref "P4") (pin "6") (pinfunction "GND_6") (pintype "power_in"))
      (node (ref "P5") (pin "4") (pinfunction "GND_4") (pintype "power_in"))
      (node (ref "P5") (pin "5") (pinfunction "GND_5") (pintype "power_in"))
      (node (ref "P5") (pin "6") (pinfunction "GND_6") (pintype "power_in"))
      (node (ref "P6") (pin "27") (pinfunction "27_27") (pintype "passive"))
      (node (ref "P6") (pin "28") (pinfunction "28_28") (pintype "passive"))
      (node (ref "R21") (pin "2") (pinfunction "2_2") (pintype "passive"))
      (node (ref "R22") (pin "2") (pinfunction "2_2") (pintype "passive"))
      (node (ref "R23") (pin "2") (pinfunction "2_2") (pintype "passive"))
      (node (ref "R24") (pin "2") (pinfunction "2_2") (pintype "passive"))
      (node (ref "R25") (pin "2") (pinfunction "2_2") (pintype "passive"))
      (node (ref "R26") (pin "2") (pinfunction "2_2") (pintype "passive"))
      (node (ref "R3") (pin "2") (pintype "passive"))
      (node (ref "R5") (pin "1") (pintype "passive"))
      (node (ref "S3") (pin "1") (pinfunction "1_1") (pintype "passive"))
      (node (ref "U1") (pin "1") (pinfunction "GND_1") (pintype "passive"))
      (node (ref "U2") (pin "0") (pinfunction "VSS_0") (pintype "power_in"))
      (node (ref "U2") (pin "12") (pinfunction "VSSA_12") (pintype "power_in"))
      (node (ref "U2") (pin "18") (pinfunction "VSS_1_18") (pintype "bidirectional"))
      (node (ref "U2") (pin "49") (pinfunction "VSS_2_49") (pintype "power_in"))
    )
    (net (code "77") (name "Net-(D1-K)") (class "Default")
      (node (ref "D1") (pin "2") (pinfunction "K_2") (pintype "passive"))
      (node (ref "R3") (pin "1") (pintype "passive"))
    )
    (net (code "78") (name "Net-(D3-A)") (class "Default")
      (node (ref "D3") (pin "1") (pinfunction "A_1") (pintype "passive"))
      (node (ref "R1") (pin "2") (pintype "passive"))
    )
    (net (code "79") (name "Net-(D4-A)") (class "Default")
      (node (ref "D4") (pin "1") (pinfunction "A_1") (pintype "passive"))
      (node (ref "R4") (pin "2") (pintype "passive"))
    )
    (net (code "80") (name "Net-(P2-Pad9)") (class "Default")
      (node (ref "P2") (pin "9") (pintype "passive"))
      (node (ref "R8") (pin "2") (pintype "passive"))
    )
    (net (code "81") (name "Net-(P2-Pad12)") (class "Default")
      (node (ref "P2") (pin "12") (pintype "passive"))
      (node (ref "R9") (pin "2") (pintype "passive"))
    )
    (net (code "82") (name "Net-(P14-CC-PadA5)") (class "Default")
      (node (ref "P14") (pin "A5") (pinfunction "CC_A5") (pintype "bidirectional"))
      (node (ref "R25") (pin "1") (pinfunction "1_1") (pintype "passive"))
    )
    (net (code "83") (name "Net-(P14-CC-PadB5)") (class "Default")
      (node (ref "P14") (pin "B5") (pinfunction "CC_B5") (pintype "bidirectional"))
      (node (ref "R26") (pin "1") (pinfunction "1_1") (pintype "passive"))
    )
    (net (code "84") (name "Net-(P15-CC-PadA5)") (class "Default")
      (node (ref "P15") (pin "A5") (pinfunction "CC_A5") (pintype "bidirectional"))
      (node (ref "R23") (pin "1") (pinfunction "1_1") (pintype "passive"))
    )
    (net (code "85") (name "Net-(P15-CC-PadB5)") (class "Default")
      (node (ref "P15") (pin "B5") (pinfunction "CC_B5") (pintype "bidirectional"))
      (node (ref "R24") (pin "1") (pinfunction "1_1") (pintype "passive"))
    )
    (net (code "86") (name "Net-(R5-Pad2)") (class "Default")
      (node (ref "R5") (pin "2") (pintype "passive"))
      (node (ref "S2") (pin "2") (pinfunction "2_2") (pintype "passive"))
    )
    (net (code "87") (name "Net-(R20-Pad2)") (class "Default")
      (node (ref "R20") (pin "2") (pinfunction "2_2") (pintype "passive"))
      (node (ref "S4") (pin "2") (pinfunction "2_2") (pintype "passive"))
    )
    (net (code "88") (name "Net-(S1-COMMON)") (class "Default")
      (node (ref "F1") (pin "2") (pinfunction "2_2") (pintype "passive"))
      (node (ref "S1") (pin "1") (pinfunction "COMMON_1") (pintype "passive"))
    )
    (net (code "89") (name "Net-(S1-NC)") (class "Default")
      (node (ref "C1") (pin "1") (pinfunction "1_1") (pintype "passive"))
      (node (ref "S1") (pin "2") (pinfunction "NC_2") (pintype "passive"))
      (node (ref "U1") (pin "3") (pinfunction "Vin_3") (pintype "passive"))
    )
    (net (code "90") (name "unconnected-(P2-Pad7)") (class "Default")
      (node (ref "P2") (pin "7") (pintype "passive"))
    )
    (net (code "91") (name "unconnected-(P14-RFU1-PadA8)") (class "Default")
      (node (ref "P14") (pin "A8") (pinfunction "RFU1_A8") (pintype "bidirectional+no_connect"))
    )
    (net (code "92") (name "unconnected-(P14-RFU1-PadB8)") (class "Default")
      (node (ref "P14") (pin "B8") (pinfunction "RFU1_B8") (pintype "bidirectional+no_connect"))
    )
    (net (code "93") (name "unconnected-(P15-RFU1-PadA8)") (class "Default")
      (node (ref "P15") (pin "A8") (pinfunction "RFU1_A8") (pintype "bidirectional+no_connect"))
    )
    (net (code "94") (name "unconnected-(P15-RFU1-PadB8)") (class "Default")
      (node (ref "P15") (pin "B8") (pinfunction "RFU1_B8") (pintype "bidirectional+no_connect"))
    )
    (net (code "95") (name "unconnected-(S1-NO-Pad3)") (class "Default")
      (node (ref "S1") (pin "3") (pinfunction "NO_3") (pintype "passive"))
    )
  )
)
